# cpu.net
KiCad netlist of a schematic drawn in Altium Designer
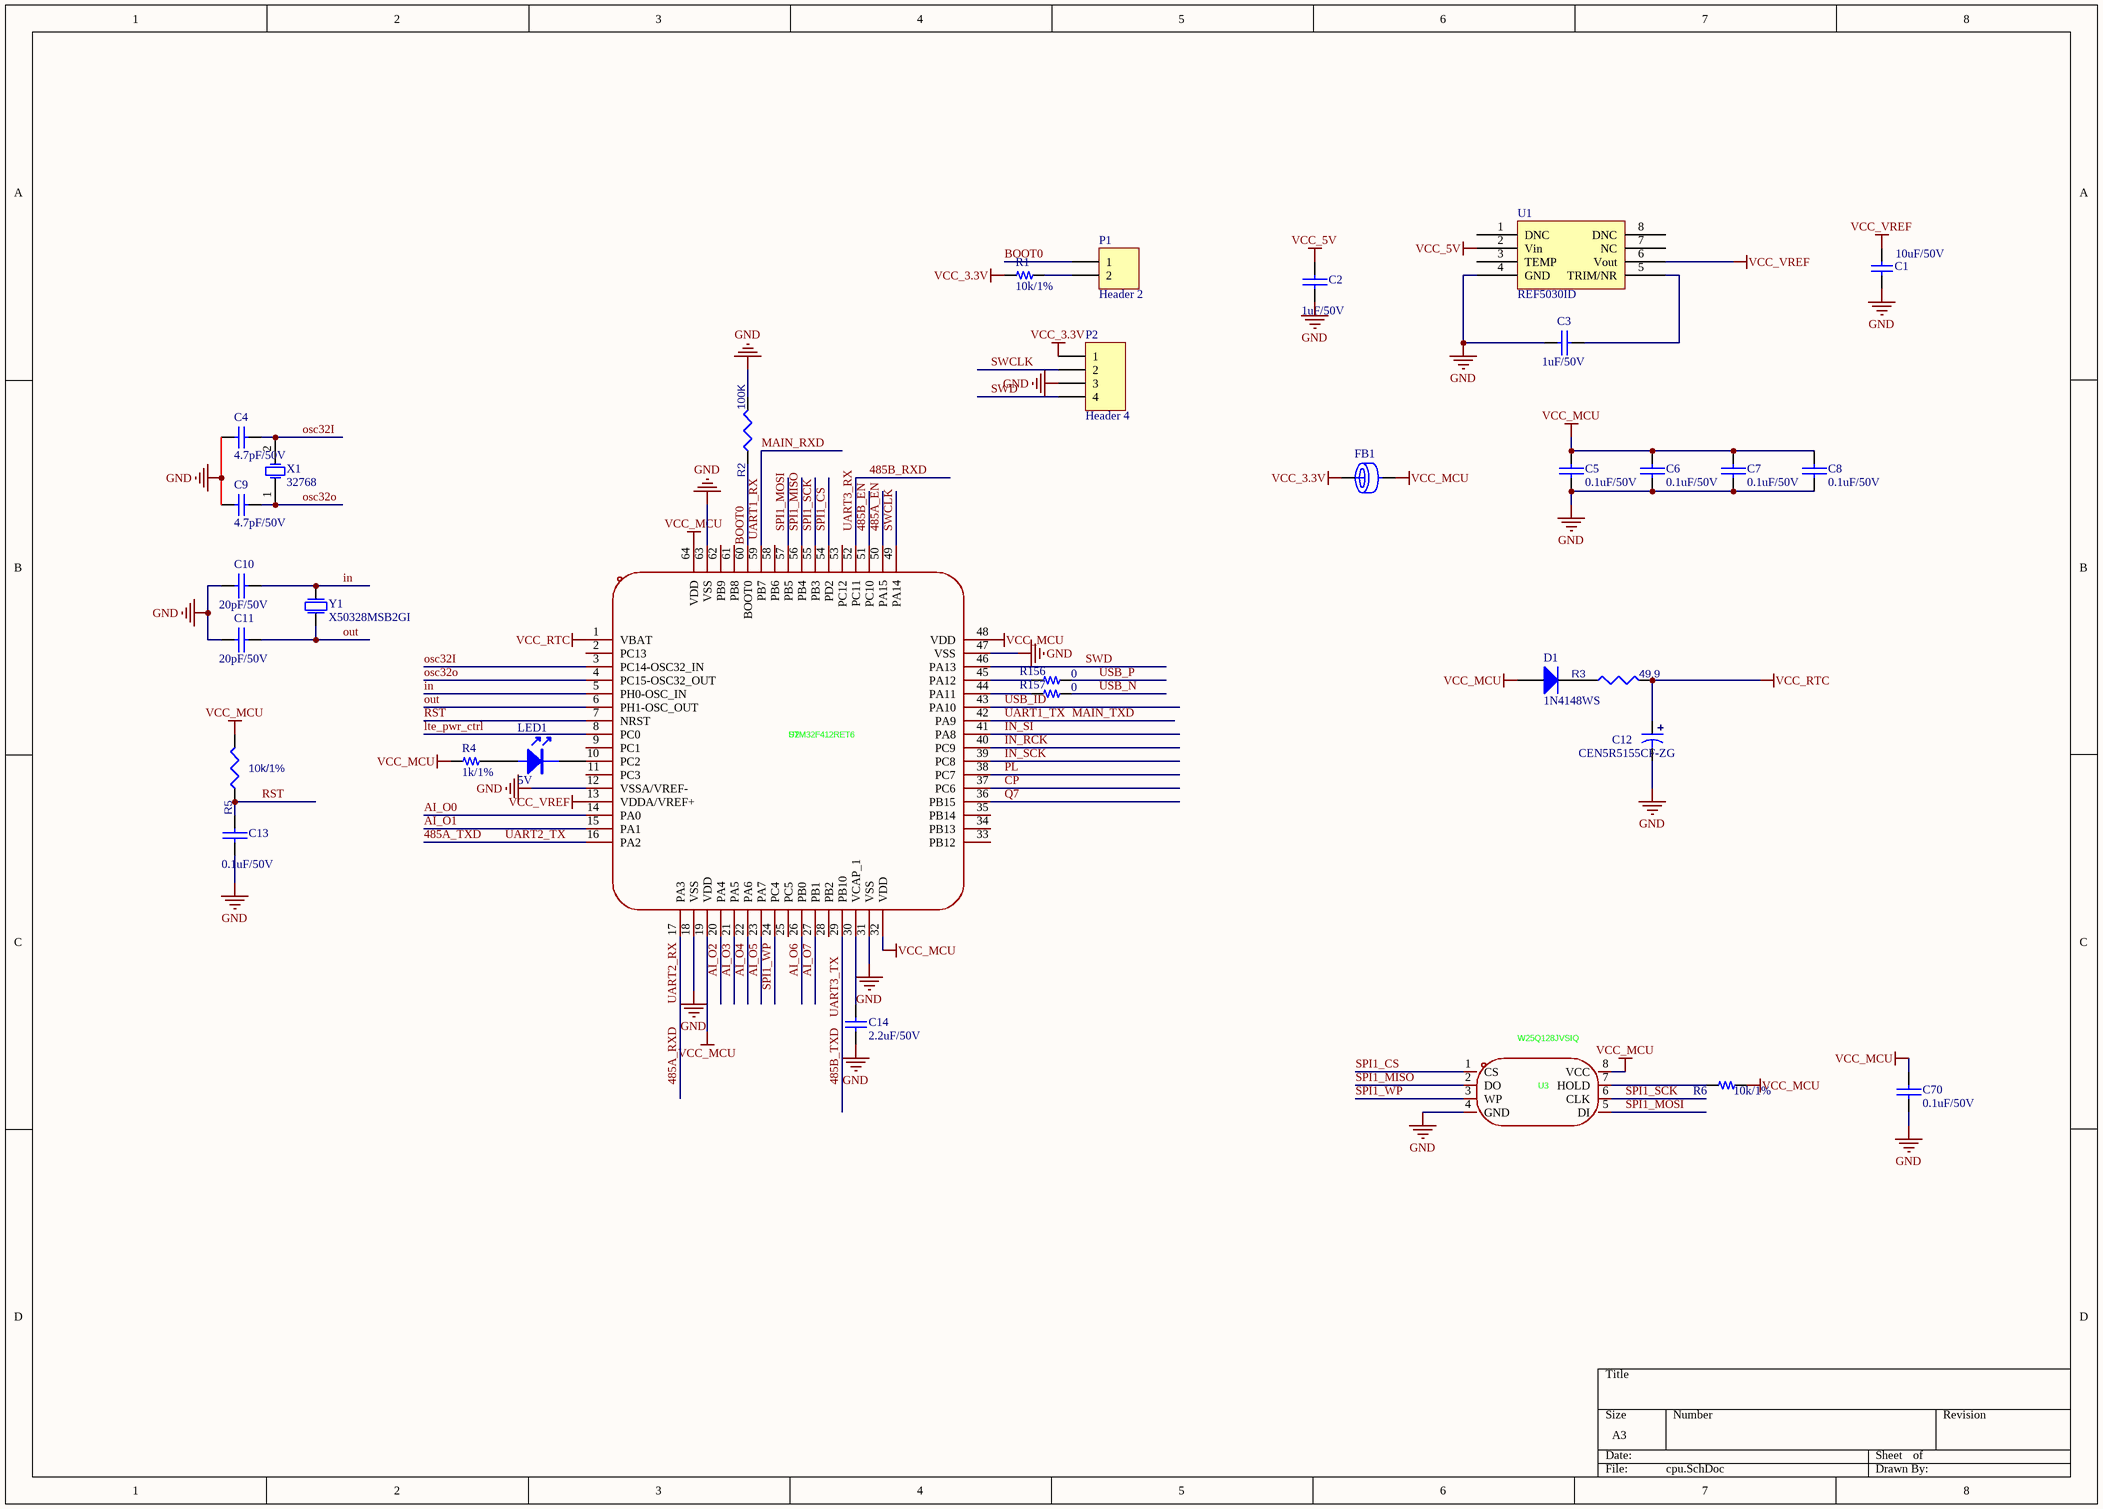
[diagram p0: cpu.SchDoc]

(export (version "E")
  (design (tool "Eeschema 10.0.6"))
  (components
    (comp (ref "C1")
      (value "10uF/50V")
      (footprint "CAPC2012X127N_0805")
      (fields (field (name "PARTNUMBER") "CL21A106KBYQNNE"))
      (libsource (lib "Miscellaneous Devices") (part "Cap"))
    )
    (comp (ref "C2")
      (value "1uF/50V")
      (footprint "CAPC1608X092N_0603")
      (fields (field (name "PARTNUMBER") "CL10A105KB8NNNC"))
      (libsource (lib "SM") (part "CAP"))
    )
    (comp (ref "C3")
      (value "1uF/50V")
      (footprint "CAPC1608X092N_0603")
      (fields (field (name "PARTNUMBER") "CL10A105KB8NNNC"))
      (libsource (lib "SM") (part "CAP"))
    )
    (comp (ref "C4")
      (value "4.7pF/50V")
      (footprint "0603C")
      (description "Capacitor")
      (libsource (lib "Miscellaneous Devices") (part "Cap"))
    )
    (comp (ref "C5")
      (value "0.1uF/50V")
      (footprint "CAPC1608X092N_0603")
      (fields (field (name "PARTNUMBER") "CC0603KRX7R9BB104"))
      (libsource (lib "SM") (part "CAP"))
    )
    (comp (ref "C6")
      (value "0.1uF/50V")
      (footprint "CAPC1608X092N_0603")
      (fields (field (name "PARTNUMBER") "CC0603KRX7R9BB104"))
      (libsource (lib "SM") (part "CAP"))
    )
    (comp (ref "C7")
      (value "0.1uF/50V")
      (footprint "CAPC1608X092N_0603")
      (fields (field (name "PARTNUMBER") "CC0603KRX7R9BB104"))
      (libsource (lib "SM") (part "CAP"))
    )
    (comp (ref "C8")
      (value "0.1uF/50V")
      (footprint "CAPC1608X092N_0603")
      (fields (field (name "PARTNUMBER") "CC0603KRX7R9BB104"))
      (libsource (lib "SM") (part "CAP"))
    )
    (comp (ref "C9")
      (value "4.7pF/50V")
      (footprint "0603C")
      (description "Capacitor")
      (libsource (lib "Miscellaneous Devices") (part "Cap"))
    )
    (comp (ref "C10")
      (value "20pF/50V")
      (footprint "CAPC1608X092N_0603")
      (fields (field (name "PARTNUMBER") "CC0603JRNPO9BN200") (field (name "Comment") "20pF/25V"))
      (libsource (lib "SM") (part "CAP"))
    )
    (comp (ref "C11")
      (value "20pF/50V")
      (footprint "CAPC1608X092N_0603")
      (fields (field (name "PARTNUMBER") "CC0603JRNPO9BN200") (field (name "Comment") "20pF/25V"))
      (libsource (lib "SM") (part "CAP"))
    )
    (comp (ref "C12")
      (value "CEN5R5155CF-ZG")
      (footprint "CAP-TH_BD21.0-P5.00-D0.8_CENXXX-CF (1):CAP-TH_BD21.0-P5.00-D0.8_CENXXX-CF")
      (description "电解电容")
      (libsource (lib "XiaoyI") (part "CAP2"))
    )
    (comp (ref "C13")
      (value "0.1uF/50V")
      (footprint "CAPC1608X092N_0603")
      (fields (field (name "PARTNUMBER") "CL10A105KB8NNNC"))
      (libsource (lib "SM") (part "CAP"))
    )
    (comp (ref "C14")
      (value "2.2uF/50V")
      (footprint "0603C")
      (description "Capacitor")
      (libsource (lib "Miscellaneous Devices") (part "Cap"))
    )
    (comp (ref "C70")
      (value "0.1uF/50V")
      (footprint "CAPC1608X092N_0603")
      (fields (field (name "PARTNUMBER") "CC0603KRX7R9BB104"))
      (libsource (lib "SM") (part "CAP"))
    )
    (comp (ref "D1") (value "1N4148WS") (footprint "SOD323") (libsource (lib "Sch_library") (part "DIODE")))
    (comp (ref "FB1")
      (value "FBC0603")
      (footprint "FBC0603")
      (fields (field (name "PARTNUMBER") "BLM18AG601SN1D"))
      (libsource (lib "Karl") (part "FBC0603"))
    )
    (comp (ref "LED1") (value "5V") (footprint "0603LED") (libsource (lib "*") (part "LED")))
    (comp (ref "P1")
      (value "Header 2")
      (footprint "HDR1X2")
      (description "Header, 2-Pin")
      (libsource (lib "Miscellaneous Connectors") (part "Header 2"))
    )
    (comp (ref "P2")
      (value "Header 4")
      (footprint "HDR1X4")
      (description "Header, 4-Pin")
      (libsource (lib "Miscellaneous Connectors") (part "Header 4"))
    )
    (comp (ref "R1")
      (value "10k/1%")
      (footprint "RESC1608X055N_0603")
      (fields (field (name "PARTNUMBER") "RC0603FR-071KL"))
      (libsource (lib "JRJ_1") (part "R"))
    )
    (comp (ref "R2") (value "100K") (footprint "0603R") (libsource (lib "*") (part "RESISTOR_0")))
    (comp (ref "R3") (value "49.9") (footprint "0603R") (libsource (lib "*") (part "RESISTOR_0")))
    (comp (ref "R4")
      (value "1k/1%")
      (footprint "RESC1608X055N_0603")
      (fields (field (name "PARTNUMBER") "RC0603FR-071KL"))
      (libsource (lib "JRJ_1") (part "R"))
    )
    (comp (ref "R5") (value "10k/1%") (footprint "0603R") (libsource (lib "*") (part "RESISTOR_0")))
    (comp (ref "R6")
      (value "10k/1%")
      (footprint "RESC1608X055N_0603")
      (fields (field (name "PARTNUMBER") "RC0603FR-071KL"))
      (libsource (lib "JRJ_1") (part "R"))
    )
    (comp (ref "R156")
      (value "0")
      (footprint "RESC1608X055N_0603")
      (fields (field (name "PARTNUMBER") "RC0603FR-071KL"))
      (libsource (lib "JRJ_1") (part "R"))
    )
    (comp (ref "R157")
      (value "0")
      (footprint "RESC1608X055N_0603")
      (fields (field (name "PARTNUMBER") "RC0603FR-071KL"))
      (libsource (lib "JRJ_1") (part "R"))
    )
    (comp (ref "U1")
      (value "REF5030ID")
      (footprint "SO-8")
      (fields (field (name "PARTNUMBER") "REF5030IDR"))
      (libsource (lib "Schlib1") (part "REF5030"))
    )
    (comp (ref "U2")
      (value "STM32F412RET6")
      (footprint "LQFP-64")
      (libsource (lib "altium-import") (part "root_0_STM32F412RET6_"))
    )
    (comp (ref "U3")
      (value "W25Q128JVSIQ")
      (footprint "so-8")
      (libsource (lib "altium-import") (part "root_0_XL1509-5.0_"))
    )
    (comp (ref "X1")
      (value "32768")
      (footprint "controller_V1.3.1:A")
      (description "Crystal Oscillator")
      (libsource (lib "Miscellaneous Devices") (part "XTAL"))
    )
    (comp (ref "Y1") (value "X50328MSB2GI") (footprint "CRAY_5032") (libsource (lib "") (part "XTAL_1")))
  )
  (nets
    (net (code "1") (name "/485A_EN") (class "Default")
      (node (ref "U2") (pin "50") (pinfunction "PA15_50") (pintype "passive"))
    )
    (net (code "2") (name "/485A_RXD") (class "Default")
      (node (ref "U2") (pin "17") (pinfunction "PA3_17") (pintype "passive"))
    )
    (net (code "3") (name "/485A_TXD") (class "Default")
      (node (ref "U2") (pin "16") (pinfunction "PA2_16") (pintype "passive"))
    )
    (net (code "4") (name "/485B_EN") (class "Default")
      (node (ref "U2") (pin "51") (pinfunction "PC10_51") (pintype "passive"))
    )
    (net (code "5") (name "/485B_RXD") (class "Default")
      (node (ref "U2") (pin "52") (pinfunction "PC11_52") (pintype "passive"))
    )
    (net (code "6") (name "/485B_TXD") (class "Default")
      (node (ref "U2") (pin "29") (pinfunction "PB10_29") (pintype "passive"))
    )
    (net (code "7") (name "/AI_O0") (class "Default")
      (node (ref "U2") (pin "14") (pinfunction "PA0_14") (pintype "passive"))
    )
    (net (code "8") (name "/AI_O1") (class "Default")
      (node (ref "U2") (pin "15") (pinfunction "PA1_15") (pintype "passive"))
    )
    (net (code "9") (name "/AI_O2") (class "Default")
      (node (ref "U2") (pin "20") (pinfunction "PA4_20") (pintype "passive"))
    )
    (net (code "10") (name "/AI_O3") (class "Default")
      (node (ref "U2") (pin "21") (pinfunction "PA5_21") (pintype "passive"))
    )
    (net (code "11") (name "/AI_O4") (class "Default")
      (node (ref "U2") (pin "22") (pinfunction "PA6_22") (pintype "passive"))
    )
    (net (code "12") (name "/AI_O5") (class "Default")
      (node (ref "U2") (pin "23") (pinfunction "PA7_23") (pintype "passive"))
    )
    (net (code "13") (name "/AI_O6") (class "Default")
      (node (ref "U2") (pin "26") (pinfunction "PB0_26") (pintype "passive"))
    )
    (net (code "14") (name "/AI_O7") (class "Default")
      (node (ref "U2") (pin "27") (pinfunction "PB1_27") (pintype "passive"))
    )
    (net (code "15") (name "/BOOT0") (class "Default")
      (node (ref "P1") (pin "1") (pinfunction "1_1") (pintype "passive"))
      (node (ref "R2") (pin "1") (pinfunction "1_1") (pintype "passive"))
      (node (ref "U2") (pin "60") (pinfunction "BOOT0_60") (pintype "passive"))
    )
    (net (code "16") (name "/CP") (class "Default")
      (node (ref "U2") (pin "37") (pinfunction "PC6_37") (pintype "passive"))
    )
    (net (code "17") (name "/IN_RCK") (class "Default")
      (node (ref "U2") (pin "40") (pinfunction "PC9_40") (pintype "passive"))
    )
    (net (code "18") (name "/IN_SCK") (class "Default")
      (node (ref "U2") (pin "39") (pinfunction "PC8_39") (pintype "passive"))
    )
    (net (code "19") (name "/IN_SI") (class "Default")
      (node (ref "U2") (pin "41") (pinfunction "PA8_41") (pintype "passive"))
    )
    (net (code "20") (name "/MAIN_RXD") (class "Default")
      (node (ref "U2") (pin "59") (pinfunction "PB7_59") (pintype "passive"))
    )
    (net (code "21") (name "/MAIN_TXD") (class "Default")
      (node (ref "U2") (pin "42") (pinfunction "PA9_42") (pintype "passive"))
    )
    (net (code "22") (name "/PL") (class "Default")
      (node (ref "U2") (pin "38") (pinfunction "PC7_38") (pintype "passive"))
    )
    (net (code "23") (name "/Q7") (class "Default")
      (node (ref "U2") (pin "36") (pinfunction "PB15_36") (pintype "passive"))
    )
    (net (code "24") (name "/RST") (class "Default")
      (node (ref "C13") (pin "2") (pinfunction "2_2") (pintype "passive"))
      (node (ref "R5") (pin "1") (pinfunction "1_1") (pintype "passive"))
      (node (ref "U2") (pin "7") (pinfunction "NRST_7") (pintype "passive"))
    )
    (net (code "25") (name "/SPI1_CS") (class "Default")
      (node (ref "U2") (pin "54") (pinfunction "PD2_54") (pintype "passive"))
      (node (ref "U3") (pin "1") (pinfunction "CS_1") (pintype "passive"))
    )
    (net (code "26") (name "/SPI1_MISO") (class "Default")
      (node (ref "U2") (pin "56") (pinfunction "PB4_56") (pintype "passive"))
      (node (ref "U3") (pin "2") (pinfunction "DO_2") (pintype "passive"))
    )
    (net (code "27") (name "/SPI1_MOSI") (class "Default")
      (node (ref "U2") (pin "57") (pinfunction "PB5_57") (pintype "passive"))
      (node (ref "U3") (pin "5") (pinfunction "DI_5") (pintype "passive"))
    )
    (net (code "28") (name "/SPI1_SCK") (class "Default")
      (node (ref "U2") (pin "55") (pinfunction "PB3_55") (pintype "passive"))
      (node (ref "U3") (pin "6") (pinfunction "CLK_6") (pintype "passive"))
    )
    (net (code "29") (name "/SPI1_WP") (class "Default")
      (node (ref "U2") (pin "24") (pinfunction "PC4_24") (pintype "passive"))
      (node (ref "U3") (pin "3") (pinfunction "WP_3") (pintype "passive"))
    )
    (net (code "30") (name "/SWCLK") (class "Default")
      (node (ref "P2") (pin "2") (pinfunction "2_2") (pintype "passive"))
      (node (ref "U2") (pin "49") (pinfunction "PA14_49") (pintype "passive"))
    )
    (net (code "31") (name "/SWD") (class "Default")
      (node (ref "P2") (pin "4") (pinfunction "4_4") (pintype "passive"))
      (node (ref "U2") (pin "46") (pinfunction "PA13_46") (pintype "passive"))
    )
    (net (code "32") (name "/USB_ID") (class "Default")
      (node (ref "U2") (pin "43") (pinfunction "PA10_43") (pintype "passive"))
    )
    (net (code "33") (name "/USB_N") (class "Default") (node (ref "R157") (pin "1") (pintype "passive")))
    (net (code "34") (name "/USB_P") (class "Default") (node (ref "R156") (pin "1") (pintype "passive")))
    (net (code "35") (name "/in") (class "Default")
      (node (ref "C10") (pin "1") (pinfunction "1_1") (pintype "passive"))
      (node (ref "U2") (pin "5") (pinfunction "PH0-OSC_IN_5") (pintype "passive"))
      (node (ref "Y1") (pin "1") (pinfunction "P1_1") (pintype "passive"))
    )
    (net (code "36") (name "/lte_pwr_ctrl") (class "Default")
      (node (ref "U2") (pin "8") (pinfunction "PC0_8") (pintype "passive"))
    )
    (net (code "37") (name "/osc32I") (class "Default")
      (node (ref "C4") (pin "1") (pinfunction "1_1") (pintype "passive"))
      (node (ref "U2") (pin "3") (pinfunction "PC14-OSC32_IN_3") (pintype "passive"))
      (node (ref "X1") (pin "2") (pinfunction "OSC2_2") (pintype "passive"))
    )
    (net (code "38") (name "/osc32o") (class "Default")
      (node (ref "C9") (pin "1") (pinfunction "1_1") (pintype "passive"))
      (node (ref "U2") (pin "4") (pinfunction "PC15-OSC32_OUT_4") (pintype "passive"))
      (node (ref "X1") (pin "1") (pinfunction "OSC1_1") (pintype "passive"))
    )
    (net (code "39") (name "/out") (class "Default")
      (node (ref "C11") (pin "1") (pinfunction "1_1") (pintype "passive"))
      (node (ref "U2") (pin "6") (pinfunction "PH1-OSC_OUT_6") (pintype "passive"))
      (node (ref "Y1") (pin "2") (pinfunction "P2_2") (pintype "passive"))
    )
    (net (code "40") (name "GND") (class "Default")
      (node (ref "C1") (pin "1") (pinfunction "1_1") (pintype "passive"))
      (node (ref "C10") (pin "2") (pinfunction "2_2") (pintype "passive"))
      (node (ref "C11") (pin "2") (pinfunction "2_2") (pintype "passive"))
      (node (ref "C12") (pin "2") (pinfunction "2_2") (pintype "passive"))
      (node (ref "C13") (pin "1") (pinfunction "1_1") (pintype "passive"))
      (node (ref "C14") (pin "2") (pinfunction "2_2") (pintype "passive"))
      (node (ref "C2") (pin "1") (pinfunction "1_1") (pintype "passive"))
      (node (ref "C3") (pin "2") (pinfunction "2_2") (pintype "passive"))
      (node (ref "C4") (pin "2") (pinfunction "2_2") (pintype "passive"))
      (node (ref "C5") (pin "1") (pinfunction "1_1") (pintype "passive"))
      (node (ref "C6") (pin "1") (pinfunction "1_1") (pintype "passive"))
      (node (ref "C7") (pin "1") (pinfunction "1_1") (pintype "passive"))
      (node (ref "C70") (pin "1") (pinfunction "1_1") (pintype "passive"))
      (node (ref "C8") (pin "1") (pinfunction "1_1") (pintype "passive"))
      (node (ref "C9") (pin "2") (pinfunction "2_2") (pintype "passive"))
      (node (ref "P2") (pin "3") (pinfunction "3_3") (pintype "passive"))
      (node (ref "R2") (pin "2") (pinfunction "2_2") (pintype "passive"))
      (node (ref "U1") (pin "4") (pinfunction "GND_4") (pintype "passive"))
      (node (ref "U2") (pin "12") (pinfunction "VSSA/VREF-_12") (pintype "passive"))
      (node (ref "U2") (pin "18") (pinfunction "VSS_18") (pintype "passive"))
      (node (ref "U2") (pin "31") (pinfunction "VSS_31") (pintype "passive"))
      (node (ref "U2") (pin "47") (pinfunction "VSS_47") (pintype "passive"))
      (node (ref "U2") (pin "63") (pinfunction "VSS_63") (pintype "passive"))
      (node (ref "U3") (pin "4") (pinfunction "GND_4") (pintype "passive"))
    )
    (net (code "41") (name "Net-(D1-K)") (class "Default")
      (node (ref "D1") (pin "2") (pinfunction "K_2") (pintype "passive"))
      (node (ref "R3") (pin "1") (pinfunction "1_1") (pintype "passive"))
    )
    (net (code "42") (name "Net-(LED1-Pad1)") (class "Default")
      (node (ref "LED1") (pin "1") (pinfunction "1_1") (pintype "passive"))
      (node (ref "R4") (pin "1") (pintype "passive"))
    )
    (net (code "43") (name "Net-(P1-Pad2)") (class "Default")
      (node (ref "P1") (pin "2") (pinfunction "2_2") (pintype "passive"))
      (node (ref "R1") (pin "2") (pintype "passive"))
    )
    (net (code "44") (name "Net-(U1-TRIM{slash}NR)") (class "Default")
      (node (ref "C3") (pin "1") (pinfunction "1_1") (pintype "passive"))
      (node (ref "U1") (pin "5") (pinfunction "TRIM/NR_5") (pintype "passive"))
    )
    (net (code "45") (name "Net-(U2-PA11)") (class "Default")
      (node (ref "R157") (pin "2") (pintype "passive"))
      (node (ref "U2") (pin "44") (pinfunction "PA11_44") (pintype "passive"))
    )
    (net (code "46") (name "Net-(U2-PA12)") (class "Default")
      (node (ref "R156") (pin "2") (pintype "passive"))
      (node (ref "U2") (pin "45") (pinfunction "PA12_45") (pintype "passive"))
    )
    (net (code "47") (name "Net-(U2-PC2)") (class "Default")
      (node (ref "LED1") (pin "2") (pinfunction "2_2") (pintype "passive"))
      (node (ref "U2") (pin "10") (pinfunction "PC2_10") (pintype "passive"))
    )
    (net (code "48") (name "Net-(U2-VCAP_1)") (class "Default")
      (node (ref "C14") (pin "1") (pinfunction "1_1") (pintype "passive"))
      (node (ref "U2") (pin "30") (pinfunction "VCAP_1_30") (pintype "passive"))
    )
    (net (code "49") (name "Net-(U3-HOLD)") (class "Default")
      (node (ref "R6") (pin "2") (pintype "passive"))
      (node (ref "U3") (pin "7") (pinfunction "HOLD_7") (pintype "passive"))
    )
    (net (code "50") (name "VCC_3.3V") (class "Default")
      (node (ref "FB1") (pin "1") (pinfunction "1_1") (pintype "passive"))
      (node (ref "P2") (pin "1") (pinfunction "1_1") (pintype "passive"))
      (node (ref "R1") (pin "1") (pintype "passive"))
    )
    (net (code "51") (name "VCC_5V") (class "Default")
      (node (ref "C2") (pin "2") (pinfunction "2_2") (pintype "passive"))
      (node (ref "U1") (pin "2") (pinfunction "Vin_2") (pintype "passive"))
    )
    (net (code "52") (name "VCC_MCU") (class "Default")
      (node (ref "C5") (pin "2") (pinfunction "2_2") (pintype "passive"))
      (node (ref "C6") (pin "2") (pinfunction "2_2") (pintype "passive"))
      (node (ref "C7") (pin "2") (pinfunction "2_2") (pintype "passive"))
      (node (ref "C70") (pin "2") (pinfunction "2_2") (pintype "passive"))
      (node (ref "C8") (pin "2") (pinfunction "2_2") (pintype "passive"))
      (node (ref "D1") (pin "1") (pinfunction "A_1") (pintype "passive"))
      (node (ref "FB1") (pin "2") (pinfunction "2_2") (pintype "passive"))
      (node (ref "R4") (pin "2") (pintype "passive"))
      (node (ref "R5") (pin "2") (pinfunction "2_2") (pintype "passive"))
      (node (ref "R6") (pin "1") (pintype "passive"))
      (node (ref "U2") (pin "19") (pinfunction "VDD_19") (pintype "passive"))
      (node (ref "U2") (pin "32") (pinfunction "VDD_32") (pintype "passive"))
      (node (ref "U2") (pin "48") (pinfunction "VDD_48") (pintype "passive"))
      (node (ref "U2") (pin "64") (pinfunction "VDD_64") (pintype "passive"))
      (node (ref "U3") (pin "8") (pinfunction "VCC_8") (pintype "passive"))
    )
    (net (code "53") (name "VCC_RTC") (class "Default")
      (node (ref "C12") (pin "1") (pinfunction "1_1") (pintype "passive"))
      (node (ref "R3") (pin "2") (pinfunction "2_2") (pintype "passive"))
      (node (ref "U2") (pin "1") (pinfunction "VBAT_1") (pintype "passive"))
    )
    (net (code "54") (name "VCC_VREF") (class "Default")
      (node (ref "C1") (pin "2") (pinfunction "2_2") (pintype "passive"))
      (node (ref "U1") (pin "6") (pinfunction "Vout_6") (pintype "passive"))
      (node (ref "U2") (pin "13") (pinfunction "VDDA/VREF+_13") (pintype "passive"))
    )
    (net (code "55") (name "unconnected-(U1-DNC-Pad1)") (class "Default")
      (node (ref "U1") (pin "1") (pinfunction "DNC_1") (pintype "passive"))
    )
    (net (code "56") (name "unconnected-(U1-DNC-Pad8)") (class "Default")
      (node (ref "U1") (pin "8") (pinfunction "DNC_8") (pintype "passive"))
    )
    (net (code "57") (name "unconnected-(U1-NC-Pad7)") (class "Default")
      (node (ref "U1") (pin "7") (pinfunction "NC_7") (pintype "passive"))
    )
    (net (code "58") (name "unconnected-(U1-TEMP-Pad3)") (class "Default")
      (node (ref "U1") (pin "3") (pinfunction "TEMP_3") (pintype "passive"))
    )
    (net (code "59") (name "unconnected-(U2-PB2-Pad28)") (class "Default")
      (node (ref "U2") (pin "28") (pinfunction "PB2_28") (pintype "passive"))
    )
    (net (code "60") (name "unconnected-(U2-PB6-Pad58)") (class "Default")
      (node (ref "U2") (pin "58") (pinfunction "PB6_58") (pintype "passive"))
    )
    (net (code "61") (name "unconnected-(U2-PB8-Pad61)") (class "Default")
      (node (ref "U2") (pin "61") (pinfunction "PB8_61") (pintype "passive"))
    )
    (net (code "62") (name "unconnected-(U2-PB9-Pad62)") (class "Default")
      (node (ref "U2") (pin "62") (pinfunction "PB9_62") (pintype "passive"))
    )
    (net (code "63") (name "unconnected-(U2-PB12-Pad33)") (class "Default")
      (node (ref "U2") (pin "33") (pinfunction "PB12_33") (pintype "passive"))
    )
    (net (code "64") (name "unconnected-(U2-PB13-Pad34)") (class "Default")
      (node (ref "U2") (pin "34") (pinfunction "PB13_34") (pintype "passive"))
    )
    (net (code "65") (name "unconnected-(U2-PB14-Pad35)") (class "Default")
      (node (ref "U2") (pin "35") (pinfunction "PB14_35") (pintype "passive"))
    )
    (net (code "66") (name "unconnected-(U2-PC1-Pad9)") (class "Default")
      (node (ref "U2") (pin "9") (pinfunction "PC1_9") (pintype "passive"))
    )
    (net (code "67") (name "unconnected-(U2-PC3-Pad11)") (class "Default")
      (node (ref "U2") (pin "11") (pinfunction "PC3_11") (pintype "passive"))
    )
    (net (code "68") (name "unconnected-(U2-PC5-Pad25)") (class "Default")
      (node (ref "U2") (pin "25") (pinfunction "PC5_25") (pintype "passive"))
    )
    (net (code "69") (name "unconnected-(U2-PC12-Pad53)") (class "Default")
      (node (ref "U2") (pin "53") (pinfunction "PC12_53") (pintype "passive"))
    )
    (net (code "70") (name "unconnected-(U2-PC13-Pad2)") (class "Default")
      (node (ref "U2") (pin "2") (pinfunction "PC13_2") (pintype "passive"))
    )
  )
)
